# serre.net
KiCad netlist of a schematic drawn in EAGLE
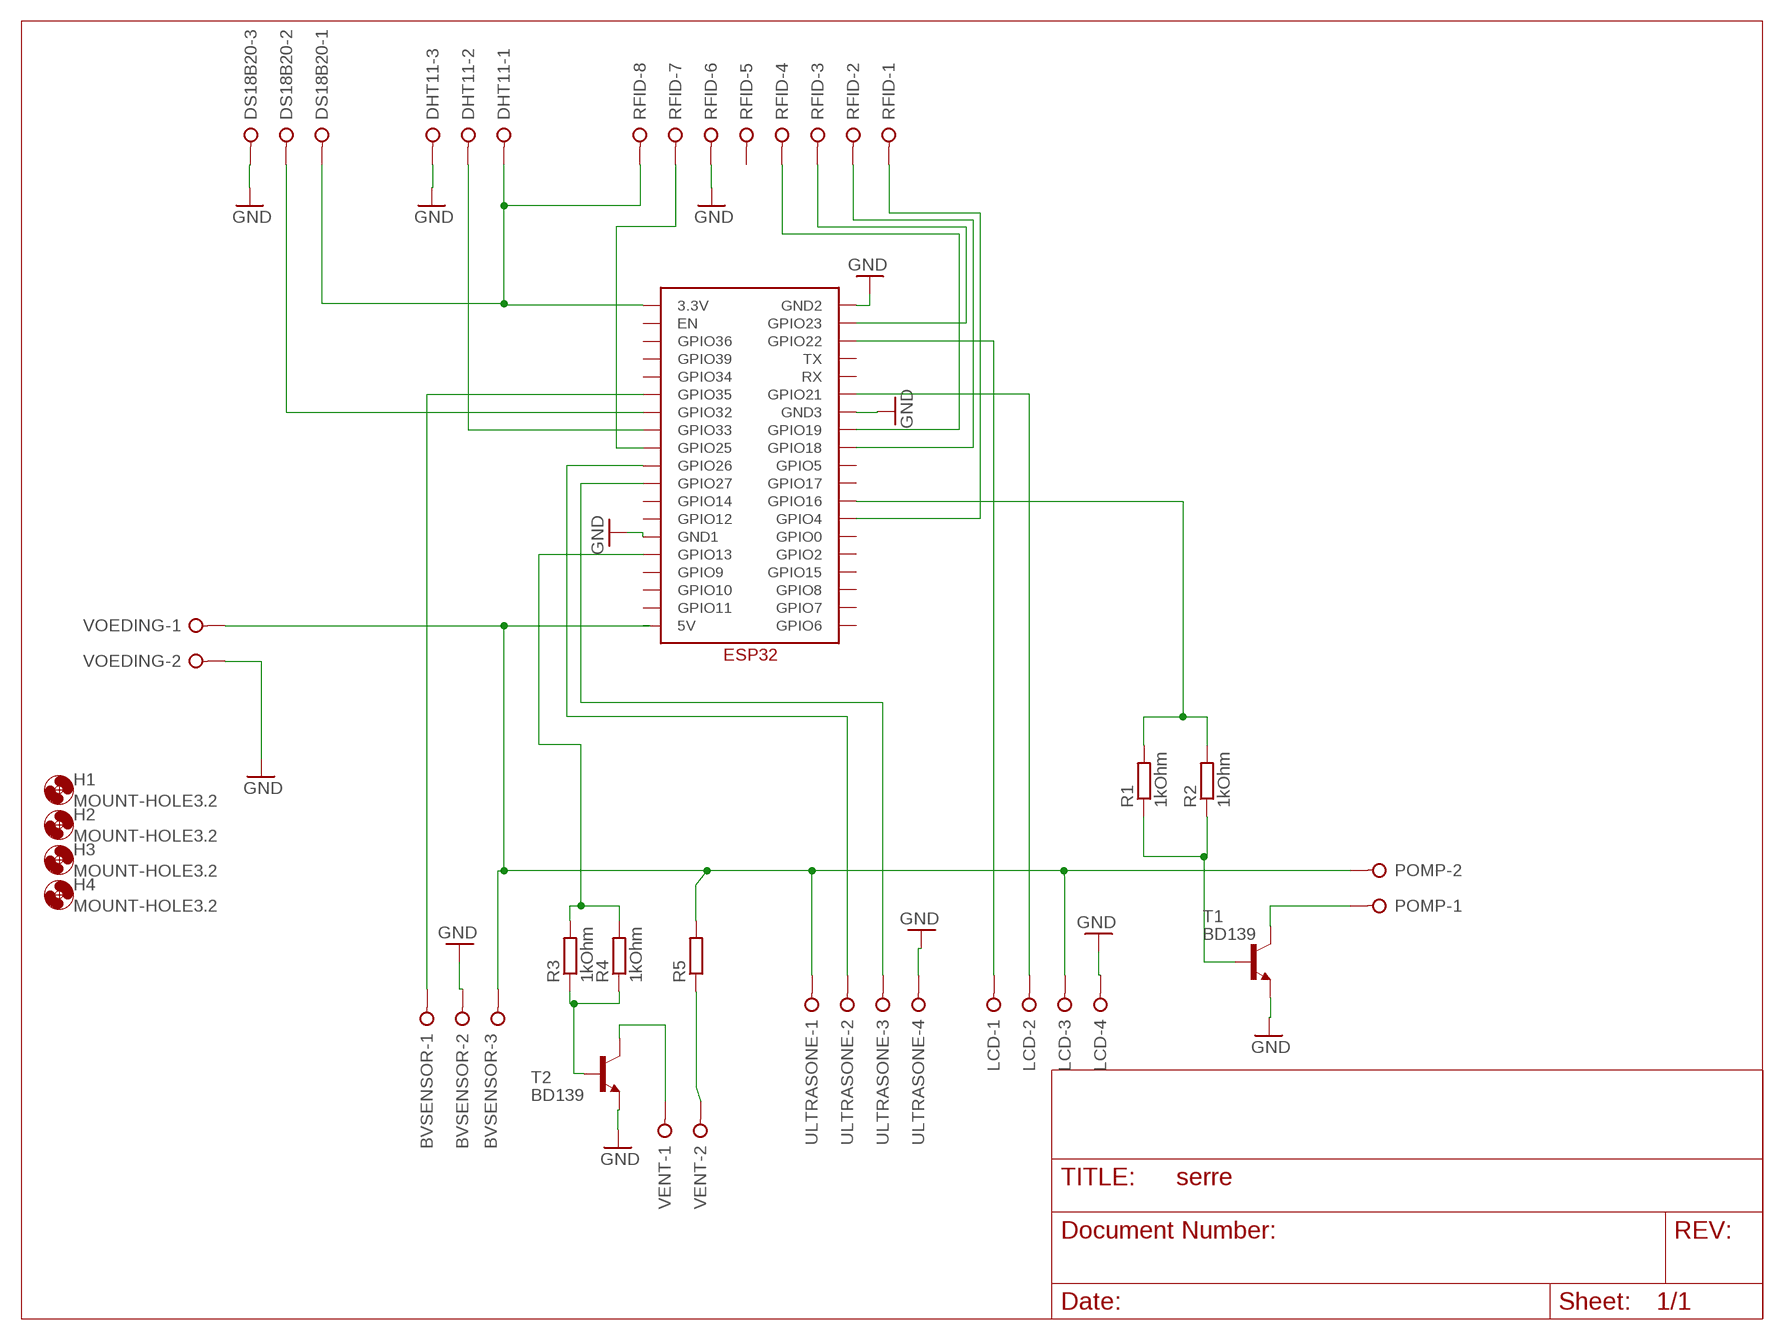
[diagram p0: schematic, sheet 1]

(export (version "E")
  (design (tool "Eeschema 10.0.6"))
  (components
    (comp (ref "BVSENSOR")
      (value "W237-03P")
      (footprint "eagle-import:W237-133")
      (libsource (lib "eagle-import") (part "W237-03P"))
    )
    (comp (ref "DHT11")
      (value "W237-03P")
      (footprint "eagle-import:W237-133")
      (libsource (lib "eagle-import") (part "W237-03P"))
    )
    (comp (ref "DS18B20")
      (value "W237-03P")
      (footprint "eagle-import:W237-133")
      (libsource (lib "eagle-import") (part "W237-03P"))
    )
    (comp (ref "H1")
      (value "MOUNT-HOLE3.2")
      (footprint "eagle-import:3,2")
      (libsource (lib "eagle-import") (part "MOUNT-HOLE3.2"))
    )
    (comp (ref "H2")
      (value "MOUNT-HOLE3.2")
      (footprint "eagle-import:3,2")
      (libsource (lib "eagle-import") (part "MOUNT-HOLE3.2"))
    )
    (comp (ref "H3")
      (value "MOUNT-HOLE3.2")
      (footprint "eagle-import:3,2")
      (libsource (lib "eagle-import") (part "MOUNT-HOLE3.2"))
    )
    (comp (ref "H4")
      (value "MOUNT-HOLE3.2")
      (footprint "eagle-import:3,2")
      (libsource (lib "eagle-import") (part "MOUNT-HOLE3.2"))
    )
    (comp (ref "LCD")
      (value "W237-04P")
      (footprint "eagle-import:W237-4P")
      (libsource (lib "eagle-import") (part "W237-04P"))
    )
    (comp (ref "POMP")
      (value "W237-02P")
      (footprint "eagle-import:W237-132")
      (libsource (lib "eagle-import") (part "W237-02P"))
    )
    (comp (ref "R1")
      (value "1kOhm")
      (footprint "eagle-import:0207_10")
      (libsource (lib "eagle-import") (part "R-EU_0207/10"))
    )
    (comp (ref "R2")
      (value "1kOhm")
      (footprint "eagle-import:0207_10")
      (libsource (lib "eagle-import") (part "R-EU_0207/10"))
    )
    (comp (ref "R3")
      (value "1kOhm")
      (footprint "eagle-import:0207_10")
      (libsource (lib "eagle-import") (part "R-EU_0207/10"))
    )
    (comp (ref "R4")
      (value "1kOhm")
      (footprint "eagle-import:0207_10")
      (libsource (lib "eagle-import") (part "R-EU_0207/10"))
    )
    (comp (ref "R5")
      (value "R-EU_0207/10")
      (footprint "eagle-import:0207_10")
      (libsource (lib "eagle-import") (part "R-EU_0207/10"))
    )
    (comp (ref "RFID")
      (value "W237-08P")
      (footprint "eagle-import:W237-8P")
      (libsource (lib "eagle-import") (part "W237-08P"))
    )
    (comp (ref "T1")
      (value "BD139")
      (footprint "eagle-import:TO126")
      (libsource (lib "eagle-import") (part "BD139"))
    )
    (comp (ref "T2")
      (value "BD139")
      (footprint "eagle-import:TO126")
      (libsource (lib "eagle-import") (part "BD139"))
    )
    (comp (ref "U$1")
      (value "ESP32")
      (footprint "eagle-import:ESP32")
      (libsource (lib "eagle-import") (part "ESP32"))
    )
    (comp (ref "ULTRASONE")
      (value "W237-04P")
      (footprint "eagle-import:W237-4P")
      (libsource (lib "eagle-import") (part "W237-04P"))
    )
    (comp (ref "VENT")
      (value "W237-02P")
      (footprint "eagle-import:W237-132")
      (libsource (lib "eagle-import") (part "W237-02P"))
    )
    (comp (ref "VOEDING")
      (value "W237-02P")
      (footprint "eagle-import:W237-132")
      (libsource (lib "eagle-import") (part "W237-02P"))
    )
  )
  (nets
    (net (code "1") (name "GND") (class "Default")
      (node (ref "BVSENSOR") (pin "2") (pinfunction "KL_2") (pintype "passive"))
      (node (ref "DHT11") (pin "3") (pinfunction "KL_3") (pintype "passive"))
      (node (ref "DS18B20") (pin "3") (pinfunction "KL_3") (pintype "passive"))
      (node (ref "LCD") (pin "4") (pinfunction "KL_4") (pintype "passive"))
      (node (ref "RFID") (pin "6") (pinfunction "KL_6") (pintype "passive"))
      (node (ref "T1") (pin "1") (pinfunction "E_1") (pintype "passive"))
      (node (ref "T2") (pin "1") (pinfunction "E_1") (pintype "passive"))
      (node (ref "U$1") (pin "GND1") (pinfunction "GND1_GND1") (pintype "bidirectional"))
      (node (ref "U$1") (pin "GND2") (pinfunction "GND2_GND2") (pintype "bidirectional"))
      (node (ref "U$1") (pin "GND3") (pinfunction "GND3_GND3") (pintype "bidirectional"))
      (node (ref "ULTRASONE") (pin "4") (pinfunction "KL_4") (pintype "passive"))
      (node (ref "VOEDING") (pin "2") (pinfunction "KL_2") (pintype "passive"))
    )
    (net (code "2") (name "Net-(BVSENSORA-KL)") (class "Default")
      (node (ref "BVSENSOR") (pin "1") (pinfunction "KL_1") (pintype "passive"))
      (node (ref "U$1") (pin "GPIO35") (pinfunction "GPIO35_GPIO35") (pintype "bidirectional"))
    )
    (net (code "3") (name "Net-(BVSENSORC-KL)") (class "Default")
      (node (ref "BVSENSOR") (pin "3") (pinfunction "KL_3") (pintype "passive"))
      (node (ref "LCD") (pin "3") (pinfunction "KL_3") (pintype "passive"))
      (node (ref "POMP") (pin "2") (pinfunction "KL_2") (pintype "passive"))
      (node (ref "R5") (pin "2") (pinfunction "2_2") (pintype "passive"))
      (node (ref "U$1") (pin "5V") (pinfunction "5V_5V") (pintype "bidirectional"))
      (node (ref "ULTRASONE") (pin "1") (pinfunction "KL_1") (pintype "passive"))
      (node (ref "VOEDING") (pin "1") (pinfunction "KL_1") (pintype "passive"))
    )
    (net (code "4") (name "Net-(DHT11A-KL)") (class "Default")
      (node (ref "DHT11") (pin "1") (pinfunction "KL_1") (pintype "passive"))
      (node (ref "DS18B20") (pin "1") (pinfunction "KL_1") (pintype "passive"))
      (node (ref "RFID") (pin "8") (pinfunction "KL_8") (pintype "passive"))
      (node (ref "U$1") (pin "3.3V") (pinfunction "3.3V_3.3V") (pintype "bidirectional"))
    )
    (net (code "5") (name "Net-(DHT11B-KL)") (class "Default")
      (node (ref "DHT11") (pin "2") (pinfunction "KL_2") (pintype "passive"))
      (node (ref "U$1") (pin "GPIO33") (pinfunction "GPIO33_GPIO33") (pintype "bidirectional"))
    )
    (net (code "6") (name "Net-(DS18B20B-KL)") (class "Default")
      (node (ref "DS18B20") (pin "2") (pinfunction "KL_2") (pintype "passive"))
      (node (ref "U$1") (pin "GPIO32") (pinfunction "GPIO32_GPIO32") (pintype "bidirectional"))
    )
    (net (code "7") (name "Net-(LCDA-KL)") (class "Default")
      (node (ref "LCD") (pin "1") (pinfunction "KL_1") (pintype "passive"))
      (node (ref "U$1") (pin "GPIO22") (pinfunction "GPIO22_GPIO22") (pintype "bidirectional"))
    )
    (net (code "8") (name "Net-(LCDB-KL)") (class "Default")
      (node (ref "LCD") (pin "2") (pinfunction "KL_2") (pintype "passive"))
      (node (ref "U$1") (pin "GPIO21") (pinfunction "GPIO21_GPIO21") (pintype "bidirectional"))
    )
    (net (code "9") (name "Net-(POMPA-KL)") (class "Default")
      (node (ref "POMP") (pin "1") (pinfunction "KL_1") (pintype "passive"))
      (node (ref "T1") (pin "2") (pinfunction "C_2") (pintype "passive"))
    )
    (net (code "10") (name "Net-(R1-Pad2)") (class "Default")
      (node (ref "R1") (pin "2") (pinfunction "2_2") (pintype "passive"))
      (node (ref "R2") (pin "2") (pinfunction "2_2") (pintype "passive"))
      (node (ref "U$1") (pin "GPIO16") (pinfunction "GPIO16_GPIO16") (pintype "bidirectional"))
    )
    (net (code "11") (name "Net-(R3-Pad2)") (class "Default")
      (node (ref "R3") (pin "2") (pinfunction "2_2") (pintype "passive"))
      (node (ref "R4") (pin "2") (pinfunction "2_2") (pintype "passive"))
      (node (ref "U$1") (pin "GPIO13") (pinfunction "GPIO13_GPIO13") (pintype "bidirectional"))
    )
    (net (code "12") (name "Net-(RFIDA-KL)") (class "Default")
      (node (ref "RFID") (pin "1") (pinfunction "KL_1") (pintype "passive"))
      (node (ref "U$1") (pin "GPIO4") (pinfunction "GPIO4_GPIO4") (pintype "bidirectional"))
    )
    (net (code "13") (name "Net-(RFIDB-KL)") (class "Default")
      (node (ref "RFID") (pin "2") (pinfunction "KL_2") (pintype "passive"))
      (node (ref "U$1") (pin "GPIO18") (pinfunction "GPIO18_GPIO18") (pintype "bidirectional"))
    )
    (net (code "14") (name "Net-(RFIDC-KL)") (class "Default")
      (node (ref "RFID") (pin "3") (pinfunction "KL_3") (pintype "passive"))
      (node (ref "U$1") (pin "GPIO23") (pinfunction "GPIO23_GPIO23") (pintype "bidirectional"))
    )
    (net (code "15") (name "Net-(RFIDD-KL)") (class "Default")
      (node (ref "RFID") (pin "4") (pinfunction "KL_4") (pintype "passive"))
      (node (ref "U$1") (pin "GPIO19") (pinfunction "GPIO19_GPIO19") (pintype "bidirectional"))
    )
    (net (code "16") (name "Net-(RFIDG-KL)") (class "Default")
      (node (ref "RFID") (pin "7") (pinfunction "KL_7") (pintype "passive"))
      (node (ref "U$1") (pin "GPIO25") (pinfunction "GPIO25_GPIO25") (pintype "bidirectional"))
    )
    (net (code "17") (name "Net-(T1-B)") (class "Default")
      (node (ref "R1") (pin "1") (pinfunction "1_1") (pintype "passive"))
      (node (ref "R2") (pin "1") (pinfunction "1_1") (pintype "passive"))
      (node (ref "T1") (pin "3") (pinfunction "B_3") (pintype "passive"))
    )
    (net (code "18") (name "Net-(T2-B)") (class "Default")
      (node (ref "R3") (pin "1") (pinfunction "1_1") (pintype "passive"))
      (node (ref "R4") (pin "1") (pinfunction "1_1") (pintype "passive"))
      (node (ref "T2") (pin "3") (pinfunction "B_3") (pintype "passive"))
    )
    (net (code "19") (name "Net-(T2-C)") (class "Default")
      (node (ref "T2") (pin "2") (pinfunction "C_2") (pintype "passive"))
      (node (ref "VENT") (pin "1") (pinfunction "KL_1") (pintype "passive"))
    )
    (net (code "20") (name "Net-(ULTRASONEB-KL)") (class "Default")
      (node (ref "U$1") (pin "GPIO26") (pinfunction "GPIO26_GPIO26") (pintype "bidirectional"))
      (node (ref "ULTRASONE") (pin "2") (pinfunction "KL_2") (pintype "passive"))
    )
    (net (code "21") (name "Net-(ULTRASONEC-KL)") (class "Default")
      (node (ref "U$1") (pin "GPIO27") (pinfunction "GPIO27_GPIO27") (pintype "bidirectional"))
      (node (ref "ULTRASONE") (pin "3") (pinfunction "KL_3") (pintype "passive"))
    )
    (net (code "22") (name "Net-(VENTB-KL)") (class "Default")
      (node (ref "R5") (pin "1") (pinfunction "1_1") (pintype "passive"))
      (node (ref "VENT") (pin "2") (pinfunction "KL_2") (pintype "passive"))
    )
    (net (code "23") (name "unconnected-(RFIDE-KL-Pad5)") (class "Default")
      (node (ref "RFID") (pin "5") (pinfunction "KL_5") (pintype "passive"))
    )
    (net (code "24") (name "unconnected-(U$1-PadEN)") (class "Default")
      (node (ref "U$1") (pin "EN") (pinfunction "EN_EN") (pintype "bidirectional"))
    )
    (net (code "25") (name "unconnected-(U$1-PadGPIO0)") (class "Default")
      (node (ref "U$1") (pin "GPIO0") (pinfunction "GPIO0_GPIO0") (pintype "bidirectional"))
    )
    (net (code "26") (name "unconnected-(U$1-PadGPIO2)") (class "Default")
      (node (ref "U$1") (pin "GPIO2") (pinfunction "GPIO2_GPIO2") (pintype "bidirectional"))
    )
    (net (code "27") (name "unconnected-(U$1-PadGPIO5)") (class "Default")
      (node (ref "U$1") (pin "GPIO5") (pinfunction "GPIO5_GPIO5") (pintype "bidirectional"))
    )
    (net (code "28") (name "unconnected-(U$1-PadGPIO6)") (class "Default")
      (node (ref "U$1") (pin "GPIO6") (pinfunction "GPIO6_GPIO6") (pintype "bidirectional"))
    )
    (net (code "29") (name "unconnected-(U$1-PadGPIO7)") (class "Default")
      (node (ref "U$1") (pin "GPIO7") (pinfunction "GPIO7_GPIO7") (pintype "bidirectional"))
    )
    (net (code "30") (name "unconnected-(U$1-PadGPIO8)") (class "Default")
      (node (ref "U$1") (pin "GPIO8") (pinfunction "GPIO8_GPIO8") (pintype "bidirectional"))
    )
    (net (code "31") (name "unconnected-(U$1-PadGPIO9)") (class "Default")
      (node (ref "U$1") (pin "GPIO9") (pinfunction "GPIO9_GPIO9") (pintype "bidirectional"))
    )
    (net (code "32") (name "unconnected-(U$1-PadGPIO10)") (class "Default")
      (node (ref "U$1") (pin "GPIO10") (pinfunction "GPIO10_GPIO10") (pintype "bidirectional"))
    )
    (net (code "33") (name "unconnected-(U$1-PadGPIO11)") (class "Default")
      (node (ref "U$1") (pin "GPIO11") (pinfunction "GPIO11_GPIO11") (pintype "bidirectional"))
    )
    (net (code "34") (name "unconnected-(U$1-PadGPIO12)") (class "Default")
      (node (ref "U$1") (pin "GPIO12") (pinfunction "GPIO12_GPIO12") (pintype "bidirectional"))
    )
    (net (code "35") (name "unconnected-(U$1-PadGPIO14)") (class "Default")
      (node (ref "U$1") (pin "GPIO14") (pinfunction "GPIO14_GPIO14") (pintype "bidirectional"))
    )
    (net (code "36") (name "unconnected-(U$1-PadGPIO15)") (class "Default")
      (node (ref "U$1") (pin "GPIO15") (pinfunction "GPIO15_GPIO15") (pintype "bidirectional"))
    )
    (net (code "37") (name "unconnected-(U$1-PadGPIO17)") (class "Default")
      (node (ref "U$1") (pin "GPIO17") (pinfunction "GPIO17_GPIO17") (pintype "bidirectional"))
    )
    (net (code "38") (name "unconnected-(U$1-PadGPIO34)") (class "Default")
      (node (ref "U$1") (pin "GPIO34") (pinfunction "GPIO34_GPIO34") (pintype "bidirectional"))
    )
    (net (code "39") (name "unconnected-(U$1-PadGPIO36)") (class "Default")
      (node (ref "U$1") (pin "GPIO36") (pinfunction "GPIO36_GPIO36") (pintype "bidirectional"))
    )
    (net (code "40") (name "unconnected-(U$1-PadGPIO39)") (class "Default")
      (node (ref "U$1") (pin "GPIO39") (pinfunction "GPIO39_GPIO39") (pintype "bidirectional"))
    )
    (net (code "41") (name "unconnected-(U$1-PadRX)") (class "Default")
      (node (ref "U$1") (pin "RX") (pinfunction "RX_RX") (pintype "bidirectional"))
    )
    (net (code "42") (name "unconnected-(U$1-PadTX)") (class "Default")
      (node (ref "U$1") (pin "TX") (pinfunction "TX_TX") (pintype "bidirectional"))
    )
  )
)
